# untitled.net
KiCad netlist of a schematic drawn in EAGLE
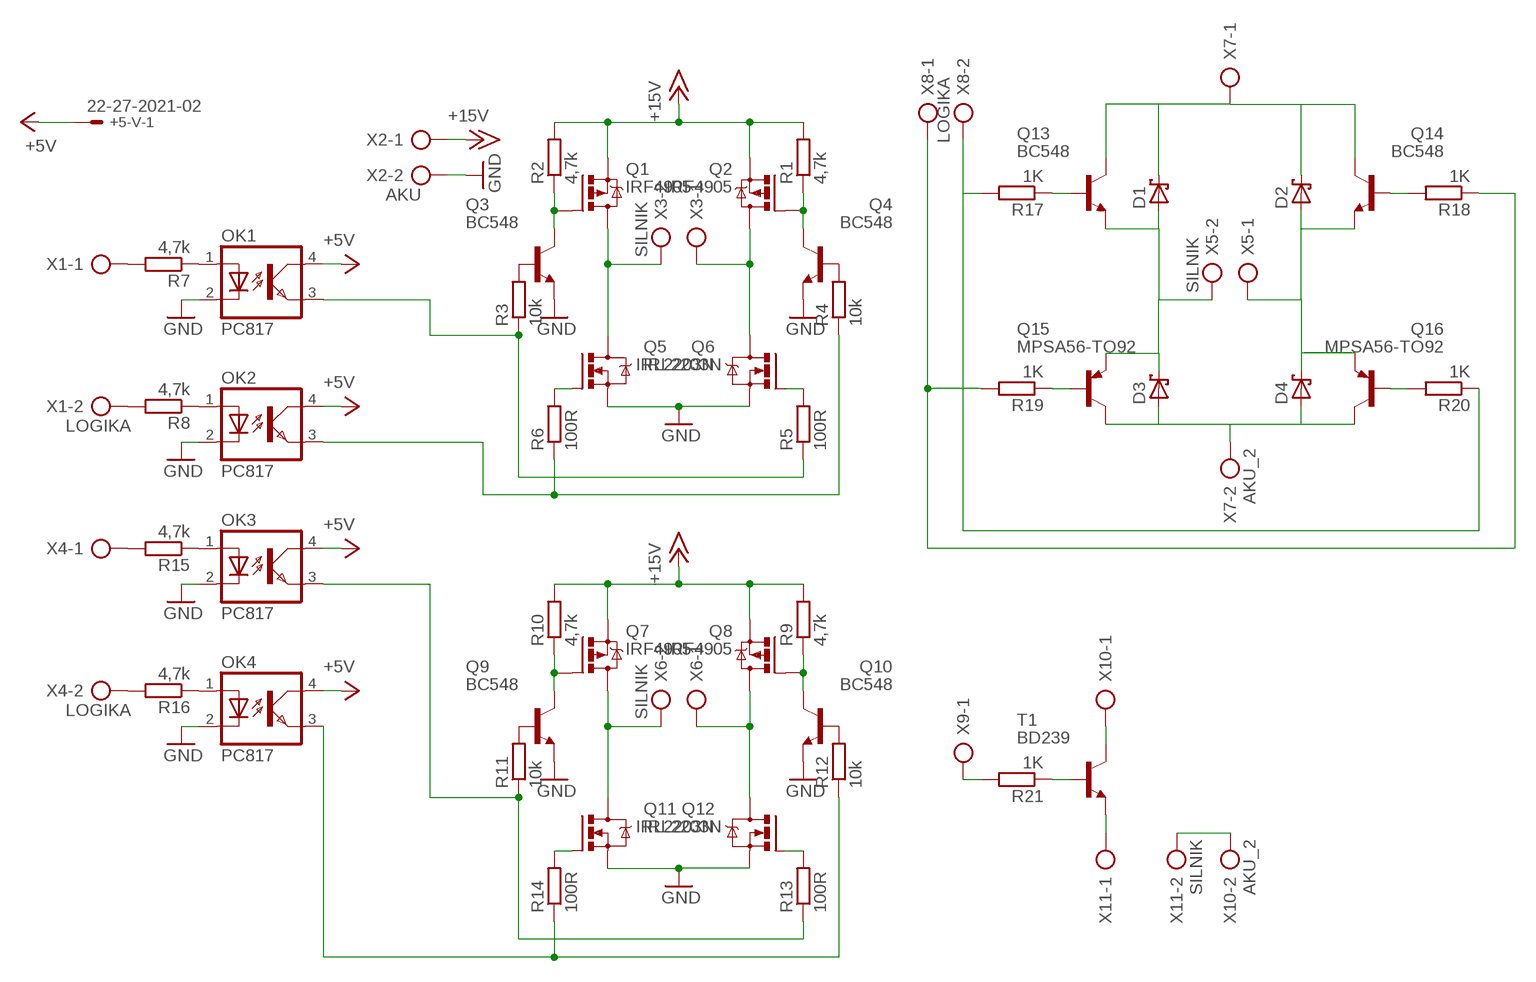
[diagram p0: schematic, sheet 1]

(export (version "E")
  (design (tool "Eeschema 10.0.6"))
  (components
    (comp (ref "+5-V")
      (value "22-27-2021-02")
      (footprint "eagle-import:6410-02")
      (libsource (lib "eagle-import") (part "22-?-0227-2021"))
    )
    (comp (ref "D1")
      (value "SCHOTTKY-DIODEDO35-7")
      (footprint "eagle-import:DO35-7")
      (libsource (lib "eagle-import") (part "SCHOTTKY-DIODEDO35-7"))
    )
    (comp (ref "D2")
      (value "SCHOTTKY-DIODEDO35-7")
      (footprint "eagle-import:DO35-7")
      (libsource (lib "eagle-import") (part "SCHOTTKY-DIODEDO35-7"))
    )
    (comp (ref "D3")
      (value "SCHOTTKY-DIODEDO35-7")
      (footprint "eagle-import:DO35-7")
      (libsource (lib "eagle-import") (part "SCHOTTKY-DIODEDO35-7"))
    )
    (comp (ref "D4")
      (value "SCHOTTKY-DIODEDO35-7")
      (footprint "eagle-import:DO35-7")
      (libsource (lib "eagle-import") (part "SCHOTTKY-DIODEDO35-7"))
    )
    (comp (ref "OK1")
      (value "PC817")
      (footprint "eagle-import:DIL04")
      (fields (field (name "MPN") "PC817X4J000F"))
      (libsource (lib "eagle-import") (part "PC817"))
    )
    (comp (ref "OK2")
      (value "PC817")
      (footprint "eagle-import:DIL04")
      (fields (field (name "MPN") "PC817X4J000F"))
      (libsource (lib "eagle-import") (part "PC817"))
    )
    (comp (ref "OK3")
      (value "PC817")
      (footprint "eagle-import:DIL04")
      (fields (field (name "MPN") "PC817X4J000F"))
      (libsource (lib "eagle-import") (part "PC817"))
    )
    (comp (ref "OK4")
      (value "PC817")
      (footprint "eagle-import:DIL04")
      (fields (field (name "MPN") "PC817X4J000F"))
      (libsource (lib "eagle-import") (part "PC817"))
    )
    (comp (ref "Q1")
      (value "IRF4905")
      (footprint "eagle-import:TO220BH")
      (libsource (lib "eagle-import") (part "IRF4905"))
    )
    (comp (ref "Q2")
      (value "IRF4905")
      (footprint "eagle-import:TO220BH")
      (libsource (lib "eagle-import") (part "IRF4905"))
    )
    (comp (ref "Q3")
      (value "BC548")
      (footprint "eagle-import:TO92-EBC")
      (libsource (lib "eagle-import") (part "BC548"))
    )
    (comp (ref "Q4")
      (value "BC548")
      (footprint "eagle-import:TO92-EBC")
      (libsource (lib "eagle-import") (part "BC548"))
    )
    (comp (ref "Q5")
      (value "IRL2203N")
      (footprint "eagle-import:TO220BV")
      (libsource (lib "eagle-import") (part "IRF540"))
    )
    (comp (ref "Q6")
      (value "IRL2203N")
      (footprint "eagle-import:TO220BV")
      (libsource (lib "eagle-import") (part "IRF540"))
    )
    (comp (ref "Q7")
      (value "IRF4905")
      (footprint "eagle-import:TO220BH")
      (libsource (lib "eagle-import") (part "IRF4905"))
    )
    (comp (ref "Q8")
      (value "IRF4905")
      (footprint "eagle-import:TO220BH")
      (libsource (lib "eagle-import") (part "IRF4905"))
    )
    (comp (ref "Q9")
      (value "BC548")
      (footprint "eagle-import:TO92-EBC")
      (libsource (lib "eagle-import") (part "BC548"))
    )
    (comp (ref "Q10")
      (value "BC548")
      (footprint "eagle-import:TO92-EBC")
      (libsource (lib "eagle-import") (part "BC548"))
    )
    (comp (ref "Q11")
      (value "IRL2203N")
      (footprint "eagle-import:TO220BV")
      (libsource (lib "eagle-import") (part "IRF540"))
    )
    (comp (ref "Q12")
      (value "IRL2203N")
      (footprint "eagle-import:TO220BV")
      (libsource (lib "eagle-import") (part "IRF540"))
    )
    (comp (ref "Q13")
      (value "BC548")
      (footprint "eagle-import:TO92-EBC")
      (libsource (lib "eagle-import") (part "BC548"))
    )
    (comp (ref "Q14")
      (value "BC548")
      (footprint "eagle-import:TO92-EBC")
      (libsource (lib "eagle-import") (part "BC548"))
    )
    (comp (ref "Q15")
      (value "MPSA56-TO92")
      (footprint "eagle-import:TO92-CBE")
      (libsource (lib "eagle-import") (part "-?TO92MPSA56"))
    )
    (comp (ref "Q16")
      (value "MPSA56-TO92")
      (footprint "eagle-import:TO92-CBE")
      (libsource (lib "eagle-import") (part "-?TO92MPSA56"))
    )
    (comp (ref "R1")
      (value "4,7k")
      (footprint "eagle-import:0207_7")
      (libsource (lib "eagle-import") (part "R-EU_0207/7"))
    )
    (comp (ref "R2")
      (value "4,7k")
      (footprint "eagle-import:0207_7")
      (libsource (lib "eagle-import") (part "R-EU_0207/7"))
    )
    (comp (ref "R3")
      (value "10k")
      (footprint "eagle-import:0207_7")
      (libsource (lib "eagle-import") (part "R-EU_0207/7"))
    )
    (comp (ref "R4")
      (value "10k")
      (footprint "eagle-import:0207_7")
      (libsource (lib "eagle-import") (part "R-EU_0207/7"))
    )
    (comp (ref "R5")
      (value "100R")
      (footprint "eagle-import:0207_7")
      (libsource (lib "eagle-import") (part "R-EU_0207/7"))
    )
    (comp (ref "R6")
      (value "100R")
      (footprint "eagle-import:0207_7")
      (libsource (lib "eagle-import") (part "R-EU_0207/7"))
    )
    (comp (ref "R7")
      (value "4,7k")
      (footprint "eagle-import:0207_7")
      (libsource (lib "eagle-import") (part "R-EU_0207/7"))
    )
    (comp (ref "R8")
      (value "4,7k")
      (footprint "eagle-import:0207_7")
      (libsource (lib "eagle-import") (part "R-EU_0207/7"))
    )
    (comp (ref "R9")
      (value "4,7k")
      (footprint "eagle-import:0207_7")
      (libsource (lib "eagle-import") (part "R-EU_0207/7"))
    )
    (comp (ref "R10")
      (value "4,7k")
      (footprint "eagle-import:0207_7")
      (libsource (lib "eagle-import") (part "R-EU_0207/7"))
    )
    (comp (ref "R11")
      (value "10k")
      (footprint "eagle-import:0207_7")
      (libsource (lib "eagle-import") (part "R-EU_0207/7"))
    )
    (comp (ref "R12")
      (value "10k")
      (footprint "eagle-import:0207_7")
      (libsource (lib "eagle-import") (part "R-EU_0207/7"))
    )
    (comp (ref "R13")
      (value "100R")
      (footprint "eagle-import:0207_7")
      (libsource (lib "eagle-import") (part "R-EU_0207/7"))
    )
    (comp (ref "R14")
      (value "100R")
      (footprint "eagle-import:0207_7")
      (libsource (lib "eagle-import") (part "R-EU_0207/7"))
    )
    (comp (ref "R15")
      (value "4,7k")
      (footprint "eagle-import:0207_7")
      (libsource (lib "eagle-import") (part "R-EU_0207/7"))
    )
    (comp (ref "R16")
      (value "4,7k")
      (footprint "eagle-import:0207_7")
      (libsource (lib "eagle-import") (part "R-EU_0207/7"))
    )
    (comp (ref "R17")
      (value "1K")
      (footprint "eagle-import:0207_7")
      (libsource (lib "eagle-import") (part "R-EU_0207/7"))
    )
    (comp (ref "R18")
      (value "1K")
      (footprint "eagle-import:0207_7")
      (libsource (lib "eagle-import") (part "R-EU_0207/7"))
    )
    (comp (ref "R19")
      (value "1K")
      (footprint "eagle-import:0207_7")
      (libsource (lib "eagle-import") (part "R-EU_0207/7"))
    )
    (comp (ref "R20")
      (value "1K")
      (footprint "eagle-import:0207_7")
      (libsource (lib "eagle-import") (part "R-EU_0207/7"))
    )
    (comp (ref "R21")
      (value "1K")
      (footprint "eagle-import:0207_7")
      (libsource (lib "eagle-import") (part "R-EU_0207/7"))
    )
    (comp (ref "T1")
      (value "BD239")
      (footprint "eagle-import:TO220")
      (libsource (lib "eagle-import") (part "BD239"))
    )
    (comp (ref "X1")
      (value "LOGIKA")
      (footprint "eagle-import:AK500_2")
      (libsource (lib "eagle-import") (part "AK500/2"))
    )
    (comp (ref "X2")
      (value "AKU")
      (footprint "eagle-import:AK500_2")
      (libsource (lib "eagle-import") (part "AK500/2"))
    )
    (comp (ref "X3")
      (value "SILNIK")
      (footprint "eagle-import:AK500_2")
      (libsource (lib "eagle-import") (part "AK500/2"))
    )
    (comp (ref "X4")
      (value "LOGIKA")
      (footprint "eagle-import:AK500_2")
      (libsource (lib "eagle-import") (part "AK500/2"))
    )
    (comp (ref "X5")
      (value "SILNIK")
      (footprint "eagle-import:AK500_2")
      (libsource (lib "eagle-import") (part "AK500/2"))
    )
    (comp (ref "X6")
      (value "SILNIK")
      (footprint "eagle-import:AK500_2")
      (libsource (lib "eagle-import") (part "AK500/2"))
    )
    (comp (ref "X7")
      (value "AKU_2")
      (footprint "eagle-import:AK500_2")
      (libsource (lib "eagle-import") (part "AK500/2"))
    )
    (comp (ref "X8")
      (value "LOGIKA")
      (footprint "eagle-import:AK500_2")
      (libsource (lib "eagle-import") (part "AK500/2"))
    )
    (comp (ref "X9")
      (value "LOGIKA")
      (footprint "eagle-import:AK500_2")
      (libsource (lib "eagle-import") (part "AK500/2"))
    )
    (comp (ref "X10")
      (value "AKU_2")
      (footprint "eagle-import:AK500_2")
      (libsource (lib "eagle-import") (part "AK500/2"))
    )
    (comp (ref "X11")
      (value "SILNIK")
      (footprint "eagle-import:AK500_2")
      (libsource (lib "eagle-import") (part "AK500/2"))
    )
  )
  (nets
    (net (code "1") (name "+5V") (class "Default")
      (node (ref "+5-V") (pin "1") (pinfunction "S_1") (pintype "passive"))
      (node (ref "OK1") (pin "4") (pinfunction "COL_4") (pintype "passive"))
      (node (ref "OK2") (pin "4") (pinfunction "COL_4") (pintype "passive"))
      (node (ref "OK3") (pin "4") (pinfunction "COL_4") (pintype "passive"))
      (node (ref "OK4") (pin "4") (pinfunction "COL_4") (pintype "passive"))
    )
    (net (code "2") (name "+15V") (class "Default")
      (node (ref "Q1") (pin "S") (pinfunction "S_S") (pintype "passive"))
      (node (ref "Q2") (pin "S") (pinfunction "S_S") (pintype "passive"))
      (node (ref "Q7") (pin "S") (pinfunction "S_S") (pintype "passive"))
      (node (ref "Q8") (pin "S") (pinfunction "S_S") (pintype "passive"))
      (node (ref "R1") (pin "2") (pinfunction "2_2") (pintype "passive"))
      (node (ref "R10") (pin "2") (pinfunction "2_2") (pintype "passive"))
      (node (ref "R2") (pin "2") (pinfunction "2_2") (pintype "passive"))
      (node (ref "R9") (pin "2") (pinfunction "2_2") (pintype "passive"))
      (node (ref "X2") (pin "1") (pinfunction "KL_1") (pintype "passive"))
    )
    (net (code "3") (name "GND") (class "Default")
      (node (ref "OK1") (pin "2") (pinfunction "C_2") (pintype "passive"))
      (node (ref "OK2") (pin "2") (pinfunction "C_2") (pintype "passive"))
      (node (ref "OK3") (pin "2") (pinfunction "C_2") (pintype "passive"))
      (node (ref "OK4") (pin "2") (pinfunction "C_2") (pintype "passive"))
      (node (ref "Q10") (pin "E") (pinfunction "E_E") (pintype "passive"))
      (node (ref "Q11") (pin "S") (pinfunction "S_S") (pintype "passive"))
      (node (ref "Q12") (pin "S") (pinfunction "S_S") (pintype "passive"))
      (node (ref "Q3") (pin "E") (pinfunction "E_E") (pintype "passive"))
      (node (ref "Q4") (pin "E") (pinfunction "E_E") (pintype "passive"))
      (node (ref "Q5") (pin "S") (pinfunction "S_S") (pintype "passive"))
      (node (ref "Q6") (pin "S") (pinfunction "S_S") (pintype "passive"))
      (node (ref "Q9") (pin "E") (pinfunction "E_E") (pintype "passive"))
      (node (ref "X2") (pin "2") (pinfunction "KL_2") (pintype "passive"))
    )
    (net (code "4") (name "Net-(OK1-A)") (class "Default")
      (node (ref "OK1") (pin "1") (pinfunction "A_1") (pintype "passive"))
      (node (ref "R7") (pin "1") (pinfunction "1_1") (pintype "passive"))
    )
    (net (code "5") (name "Net-(OK1-EMIT)") (class "Default")
      (node (ref "OK1") (pin "3") (pinfunction "EMIT_3") (pintype "passive"))
      (node (ref "R3") (pin "1") (pinfunction "1_1") (pintype "passive"))
      (node (ref "R5") (pin "1") (pinfunction "1_1") (pintype "passive"))
    )
    (net (code "6") (name "Net-(OK2-A)") (class "Default")
      (node (ref "OK2") (pin "1") (pinfunction "A_1") (pintype "passive"))
      (node (ref "R8") (pin "1") (pinfunction "1_1") (pintype "passive"))
    )
    (net (code "7") (name "Net-(OK2-EMIT)") (class "Default")
      (node (ref "OK2") (pin "3") (pinfunction "EMIT_3") (pintype "passive"))
      (node (ref "R4") (pin "1") (pinfunction "1_1") (pintype "passive"))
      (node (ref "R6") (pin "1") (pinfunction "1_1") (pintype "passive"))
    )
    (net (code "8") (name "Net-(OK3-A)") (class "Default")
      (node (ref "OK3") (pin "1") (pinfunction "A_1") (pintype "passive"))
      (node (ref "R15") (pin "1") (pinfunction "1_1") (pintype "passive"))
    )
    (net (code "9") (name "Net-(OK3-EMIT)") (class "Default")
      (node (ref "OK3") (pin "3") (pinfunction "EMIT_3") (pintype "passive"))
      (node (ref "R11") (pin "1") (pinfunction "1_1") (pintype "passive"))
      (node (ref "R13") (pin "1") (pinfunction "1_1") (pintype "passive"))
    )
    (net (code "10") (name "Net-(OK4-A)") (class "Default")
      (node (ref "OK4") (pin "1") (pinfunction "A_1") (pintype "passive"))
      (node (ref "R16") (pin "1") (pinfunction "1_1") (pintype "passive"))
    )
    (net (code "11") (name "Net-(OK4-EMIT)") (class "Default")
      (node (ref "OK4") (pin "3") (pinfunction "EMIT_3") (pintype "passive"))
      (node (ref "R12") (pin "1") (pinfunction "1_1") (pintype "passive"))
      (node (ref "R14") (pin "1") (pinfunction "1_1") (pintype "passive"))
    )
    (net (code "12") (name "Net-(Q1-PadG)") (class "Default")
      (node (ref "Q1") (pin "G") (pinfunction "G_G") (pintype "passive"))
      (node (ref "Q3") (pin "C") (pinfunction "C_C") (pintype "passive"))
      (node (ref "R2") (pin "1") (pinfunction "1_1") (pintype "passive"))
    )
    (net (code "13") (name "Net-(Q2-PadG)") (class "Default")
      (node (ref "Q2") (pin "G") (pinfunction "G_G") (pintype "passive"))
      (node (ref "Q4") (pin "C") (pinfunction "C_C") (pintype "passive"))
      (node (ref "R1") (pin "1") (pinfunction "1_1") (pintype "passive"))
    )
    (net (code "14") (name "Net-(Q3-PadB)") (class "Default")
      (node (ref "Q3") (pin "B") (pinfunction "B_B") (pintype "passive"))
      (node (ref "R3") (pin "2") (pinfunction "2_2") (pintype "passive"))
    )
    (net (code "15") (name "Net-(Q4-PadB)") (class "Default")
      (node (ref "Q4") (pin "B") (pinfunction "B_B") (pintype "passive"))
      (node (ref "R4") (pin "2") (pinfunction "2_2") (pintype "passive"))
    )
    (net (code "16") (name "Net-(Q5-PadG)") (class "Default")
      (node (ref "Q5") (pin "G") (pinfunction "G_G") (pintype "passive"))
      (node (ref "R6") (pin "2") (pinfunction "2_2") (pintype "passive"))
    )
    (net (code "17") (name "Net-(Q6-PadG)") (class "Default")
      (node (ref "Q6") (pin "G") (pinfunction "G_G") (pintype "passive"))
      (node (ref "R5") (pin "2") (pinfunction "2_2") (pintype "passive"))
    )
    (net (code "18") (name "Net-(Q7-PadG)") (class "Default")
      (node (ref "Q7") (pin "G") (pinfunction "G_G") (pintype "passive"))
      (node (ref "Q9") (pin "C") (pinfunction "C_C") (pintype "passive"))
      (node (ref "R10") (pin "1") (pinfunction "1_1") (pintype "passive"))
    )
    (net (code "19") (name "Net-(Q9-PadB)") (class "Default")
      (node (ref "Q9") (pin "B") (pinfunction "B_B") (pintype "passive"))
      (node (ref "R11") (pin "2") (pinfunction "2_2") (pintype "passive"))
    )
    (net (code "20") (name "Net-(Q10-PadB)") (class "Default")
      (node (ref "Q10") (pin "B") (pinfunction "B_B") (pintype "passive"))
      (node (ref "R12") (pin "2") (pinfunction "2_2") (pintype "passive"))
    )
    (net (code "21") (name "Net-(Q10-PadC)") (class "Default")
      (node (ref "Q10") (pin "C") (pinfunction "C_C") (pintype "passive"))
      (node (ref "Q8") (pin "G") (pinfunction "G_G") (pintype "passive"))
      (node (ref "R9") (pin "1") (pinfunction "1_1") (pintype "passive"))
    )
    (net (code "22") (name "Net-(Q11-PadG)") (class "Default")
      (node (ref "Q11") (pin "G") (pinfunction "G_G") (pintype "passive"))
      (node (ref "R14") (pin "2") (pinfunction "2_2") (pintype "passive"))
    )
    (net (code "23") (name "Net-(Q12-PadG)") (class "Default")
      (node (ref "Q12") (pin "G") (pinfunction "G_G") (pintype "passive"))
      (node (ref "R13") (pin "2") (pinfunction "2_2") (pintype "passive"))
    )
    (net (code "24") (name "Net-(Q13-PadB)") (class "Default")
      (node (ref "Q13") (pin "B") (pinfunction "B_B") (pintype "passive"))
      (node (ref "R17") (pin "1") (pinfunction "1_1") (pintype "passive"))
    )
    (net (code "25") (name "Net-(Q14-PadB)") (class "Default")
      (node (ref "Q14") (pin "B") (pinfunction "B_B") (pintype "passive"))
      (node (ref "R18") (pin "2") (pinfunction "2_2") (pintype "passive"))
    )
    (net (code "26") (name "Net-(Q15-PadB)") (class "Default")
      (node (ref "Q15") (pin "B") (pinfunction "B_B") (pintype "passive"))
      (node (ref "R19") (pin "1") (pinfunction "1_1") (pintype "passive"))
    )
    (net (code "27") (name "Net-(Q16-PadB)") (class "Default")
      (node (ref "Q16") (pin "B") (pinfunction "B_B") (pintype "passive"))
      (node (ref "R20") (pin "2") (pinfunction "2_2") (pintype "passive"))
    )
    (net (code "28") (name "Net-(T1-B)") (class "Default")
      (node (ref "R21") (pin "1") (pinfunction "1_1") (pintype "passive"))
      (node (ref "T1") (pin "1") (pinfunction "B_1") (pintype "passive"))
    )
    (net (code "29") (name "Net-(T1-C)") (class "Default")
      (node (ref "T1") (pin "2") (pinfunction "C_2") (pintype "passive"))
      (node (ref "X10") (pin "1") (pinfunction "KL_1") (pintype "passive"))
    )
    (net (code "30") (name "Net-(T1-E)") (class "Default")
      (node (ref "T1") (pin "3") (pinfunction "E_3") (pintype "passive"))
      (node (ref "X11") (pin "1") (pinfunction "KL_1") (pintype "passive"))
    )
    (net (code "31") (name "Net-(X1A-KL)") (class "Default")
      (node (ref "R7") (pin "2") (pinfunction "2_2") (pintype "passive"))
      (node (ref "X1") (pin "1") (pinfunction "KL_1") (pintype "passive"))
    )
    (net (code "32") (name "Net-(X1B-KL)") (class "Default")
      (node (ref "R8") (pin "2") (pinfunction "2_2") (pintype "passive"))
      (node (ref "X1") (pin "2") (pinfunction "KL_2") (pintype "passive"))
    )
    (net (code "33") (name "Net-(X3A-KL)") (class "Default")
      (node (ref "Q2") (pin "D") (pinfunction "D_D") (pintype "passive"))
      (node (ref "Q6") (pin "D") (pinfunction "D_D") (pintype "passive"))
      (node (ref "X3") (pin "1") (pinfunction "KL_1") (pintype "passive"))
    )
    (net (code "34") (name "Net-(X3B-KL)") (class "Default")
      (node (ref "Q1") (pin "D") (pinfunction "D_D") (pintype "passive"))
      (node (ref "Q5") (pin "D") (pinfunction "D_D") (pintype "passive"))
      (node (ref "X3") (pin "2") (pinfunction "KL_2") (pintype "passive"))
    )
    (net (code "35") (name "Net-(X4A-KL)") (class "Default")
      (node (ref "R15") (pin "2") (pinfunction "2_2") (pintype "passive"))
      (node (ref "X4") (pin "1") (pinfunction "KL_1") (pintype "passive"))
    )
    (net (code "36") (name "Net-(X4B-KL)") (class "Default")
      (node (ref "R16") (pin "2") (pinfunction "2_2") (pintype "passive"))
      (node (ref "X4") (pin "2") (pinfunction "KL_2") (pintype "passive"))
    )
    (net (code "37") (name "Net-(X5A-KL)") (class "Default")
      (node (ref "D2") (pin "A") (pinfunction "A_A") (pintype "passive"))
      (node (ref "D4") (pin "C") (pinfunction "C_C") (pintype "passive"))
      (node (ref "Q14") (pin "E") (pinfunction "E_E") (pintype "passive"))
      (node (ref "Q16") (pin "E") (pinfunction "E_E") (pintype "passive"))
      (node (ref "X5") (pin "1") (pinfunction "KL_1") (pintype "passive"))
    )
    (net (code "38") (name "Net-(X5B-KL)") (class "Default")
      (node (ref "D1") (pin "A") (pinfunction "A_A") (pintype "passive"))
      (node (ref "D3") (pin "C") (pinfunction "C_C") (pintype "passive"))
      (node (ref "Q13") (pin "E") (pinfunction "E_E") (pintype "passive"))
      (node (ref "Q15") (pin "E") (pinfunction "E_E") (pintype "passive"))
      (node (ref "X5") (pin "2") (pinfunction "KL_2") (pintype "passive"))
    )
    (net (code "39") (name "Net-(X6A-KL)") (class "Default")
      (node (ref "Q12") (pin "D") (pinfunction "D_D") (pintype "passive"))
      (node (ref "Q8") (pin "D") (pinfunction "D_D") (pintype "passive"))
      (node (ref "X6") (pin "1") (pinfunction "KL_1") (pintype "passive"))
    )
    (net (code "40") (name "Net-(X6B-KL)") (class "Default")
      (node (ref "Q11") (pin "D") (pinfunction "D_D") (pintype "passive"))
      (node (ref "Q7") (pin "D") (pinfunction "D_D") (pintype "passive"))
      (node (ref "X6") (pin "2") (pinfunction "KL_2") (pintype "passive"))
    )
    (net (code "41") (name "Net-(X7A-KL)") (class "Default")
      (node (ref "D1") (pin "C") (pinfunction "C_C") (pintype "passive"))
      (node (ref "D2") (pin "C") (pinfunction "C_C") (pintype "passive"))
      (node (ref "Q13") (pin "C") (pinfunction "C_C") (pintype "passive"))
      (node (ref "Q14") (pin "C") (pinfunction "C_C") (pintype "passive"))
      (node (ref "X7") (pin "1") (pinfunction "KL_1") (pintype "passive"))
    )
    (net (code "42") (name "Net-(X7B-KL)") (class "Default")
      (node (ref "D3") (pin "A") (pinfunction "A_A") (pintype "passive"))
      (node (ref "D4") (pin "A") (pinfunction "A_A") (pintype "passive"))
      (node (ref "Q15") (pin "C") (pinfunction "C_C") (pintype "passive"))
      (node (ref "Q16") (pin "C") (pinfunction "C_C") (pintype "passive"))
      (node (ref "X7") (pin "2") (pinfunction "KL_2") (pintype "passive"))
    )
    (net (code "43") (name "Net-(X8A-KL)") (class "Default")
      (node (ref "R18") (pin "1") (pinfunction "1_1") (pintype "passive"))
      (node (ref "R19") (pin "2") (pinfunction "2_2") (pintype "passive"))
      (node (ref "X8") (pin "1") (pinfunction "KL_1") (pintype "passive"))
    )
    (net (code "44") (name "Net-(X8B-KL)") (class "Default")
      (node (ref "R17") (pin "2") (pinfunction "2_2") (pintype "passive"))
      (node (ref "R20") (pin "1") (pinfunction "1_1") (pintype "passive"))
      (node (ref "X8") (pin "2") (pinfunction "KL_2") (pintype "passive"))
    )
    (net (code "45") (name "Net-(X9A-KL)") (class "Default")
      (node (ref "R21") (pin "2") (pinfunction "2_2") (pintype "passive"))
      (node (ref "X9") (pin "1") (pinfunction "KL_1") (pintype "passive"))
    )
    (net (code "46") (name "Net-(X10B-KL)") (class "Default")
      (node (ref "X10") (pin "2") (pinfunction "KL_2") (pintype "passive"))
      (node (ref "X11") (pin "2") (pinfunction "KL_2") (pintype "passive"))
    )
  )
)
